# powerswitch.net
KiCad netlist of a schematic drawn in Altium Designer
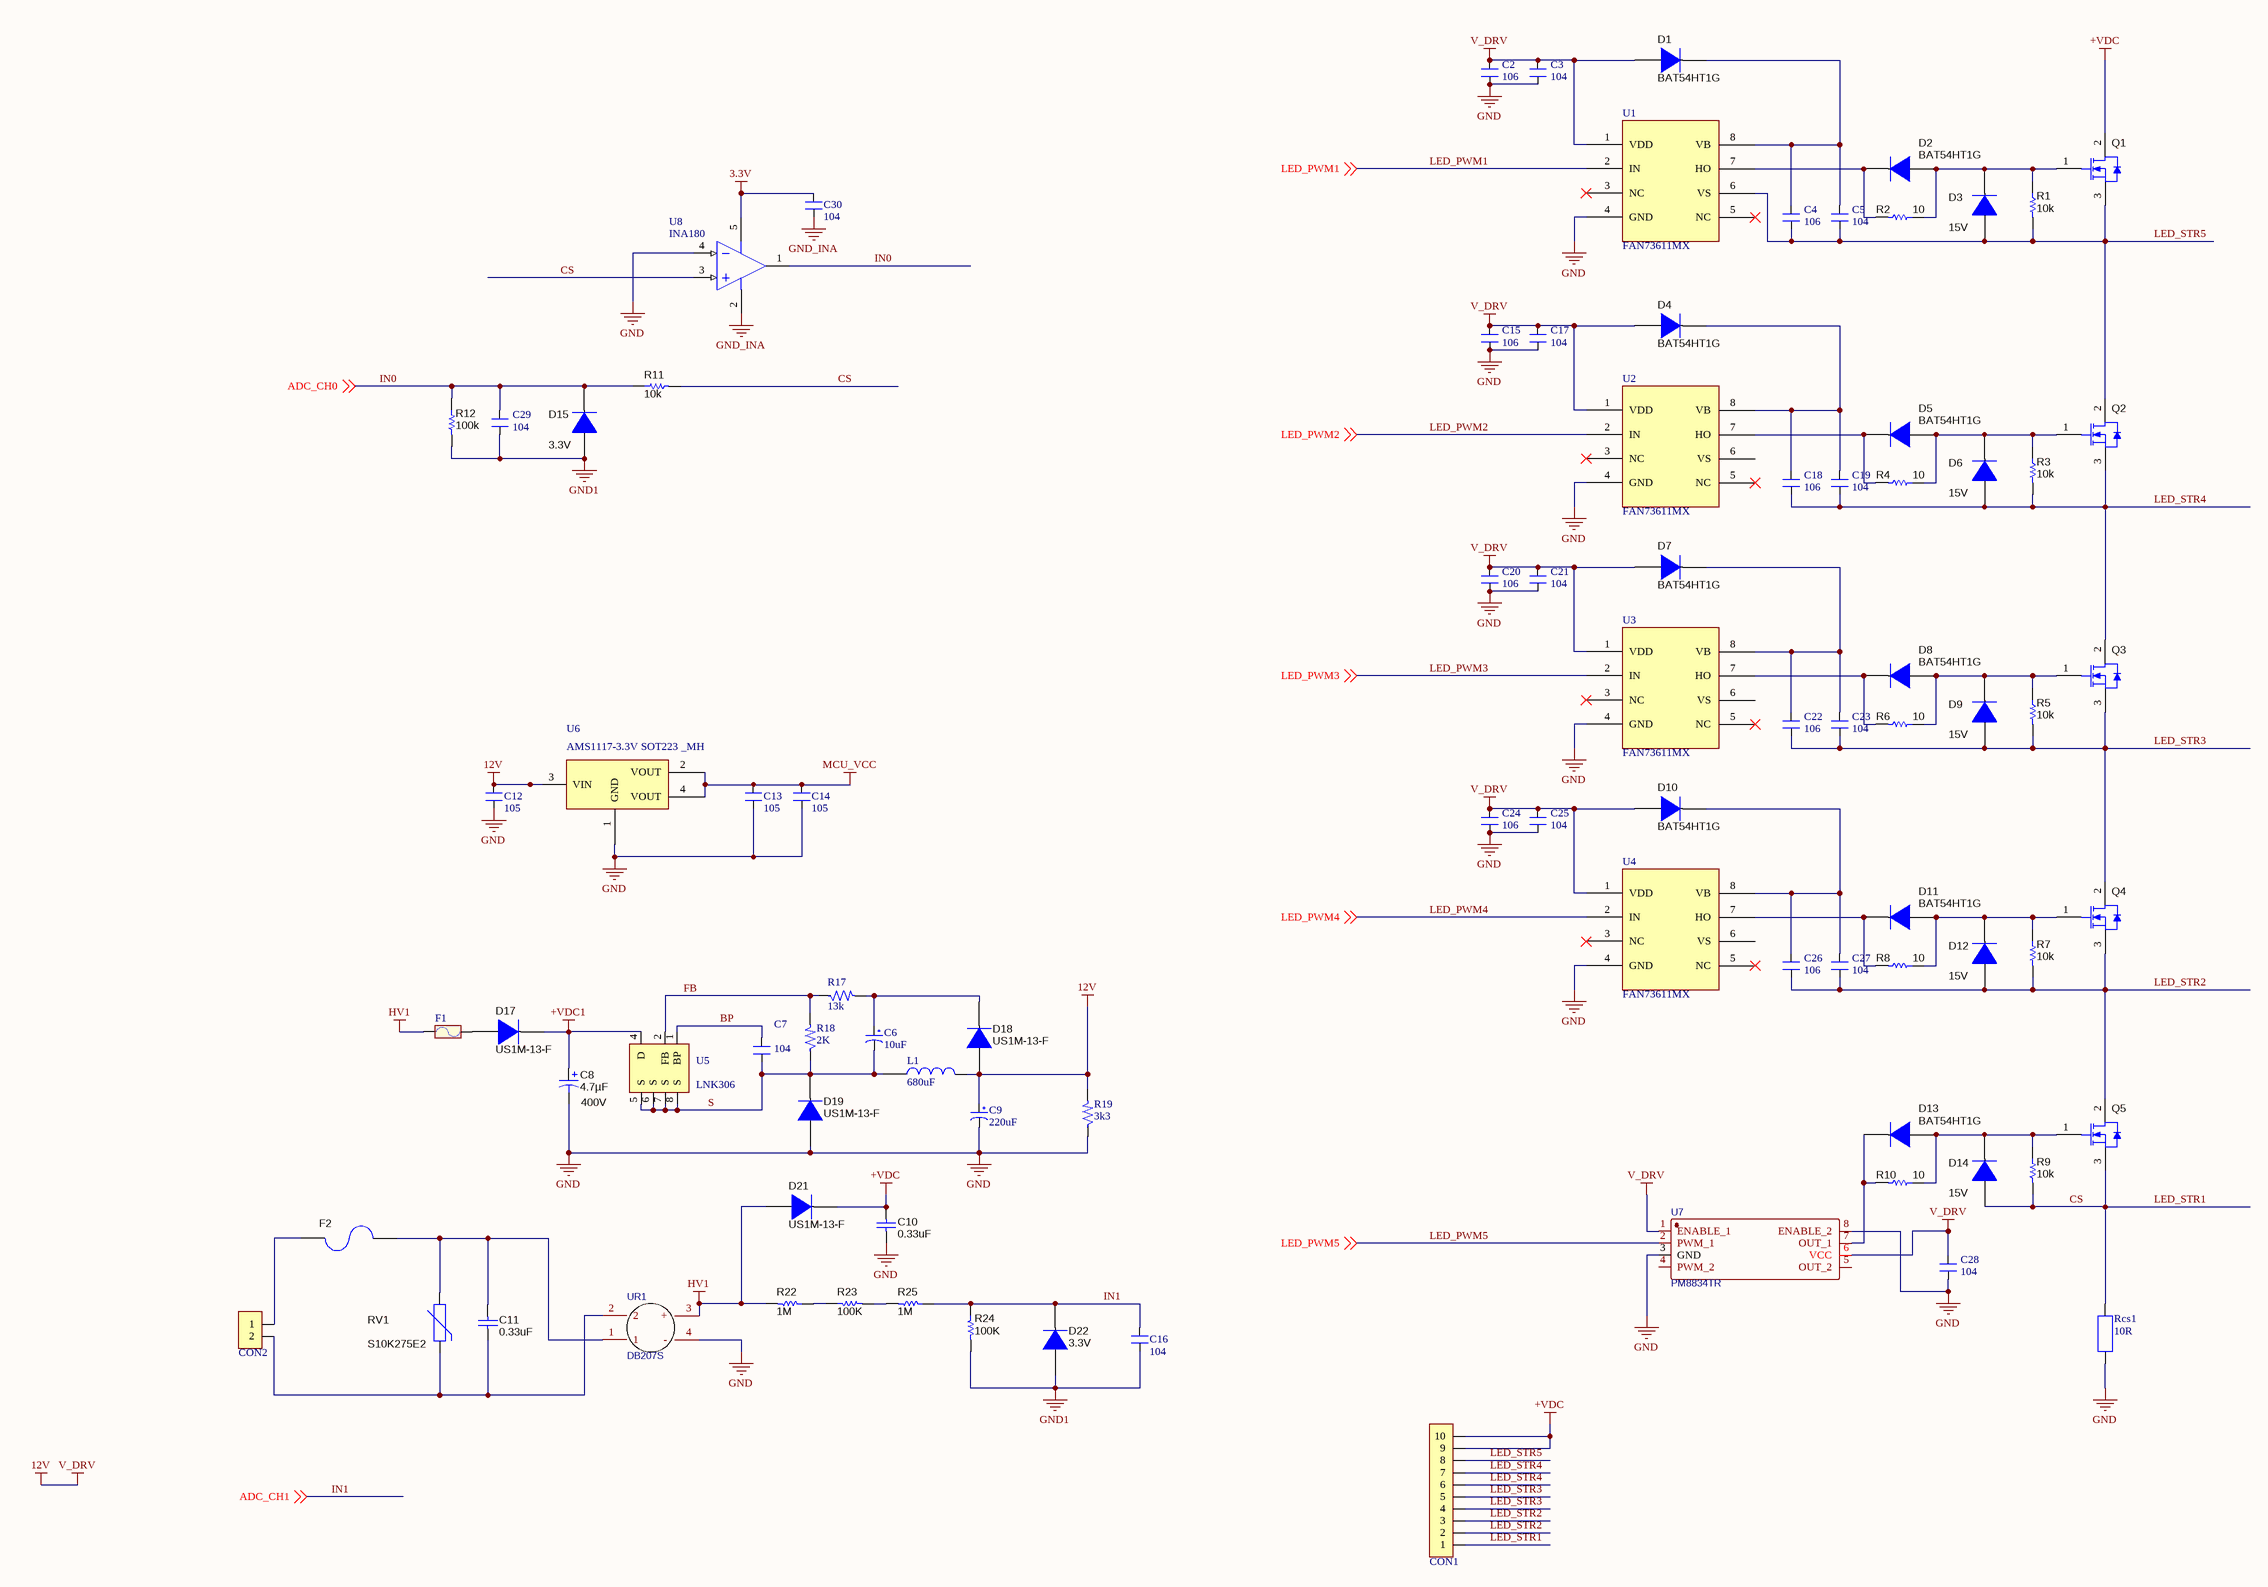
[diagram p0: powerswitch.SchDoc]

(export (version "E")
  (design (tool "Eeschema 10.0.6"))
  (components
    (comp (ref "C2")
      (value "106")
      (footprint "0805_HV")
      (description "Cap SMD")
      (libsource (lib "hatcatbietbay") (part "CM"))
    )
    (comp (ref "C3")
      (value "104")
      (footprint "0805_HV")
      (description "Cap SMD")
      (libsource (lib "hatcatbietbay") (part "CM"))
    )
    (comp (ref "C4")
      (value "106")
      (footprint "0805_HV")
      (description "Cap SMD")
      (libsource (lib "hatcatbietbay") (part "CM"))
    )
    (comp (ref "C5")
      (value "104")
      (footprint "0805_HV")
      (description "Cap SMD")
      (libsource (lib "hatcatbietbay") (part "CM"))
    )
    (comp (ref "C6")
      (value "10uF")
      (footprint "TU_NHOM_10uF_MH")
      (description "TU_NHOM_10uF_25V_MH")
      (libsource (lib "MH_DA_THU_VIEN_16122016") (part "TU_NHOM_10uF_25V_MH"))
    )
    (comp (ref "C7")
      (value "104")
      (footprint "0805_HV")
      (description "Cap SMD")
      (libsource (lib "hatcatbietbay") (part "CM"))
    )
    (comp (ref "C8")
      (value "400AX6R8M8x11")
      (footprint "CAP-PANACAP-G-GENERIC")
      (description "CAP, AL, 6.8uF, 400V, +/-20%, TH")
      (fields
        (field (name "VALUEDISPLAYED") "4.7µF")
        (field (name "MANUFACTURER") "Rubycon")
        (field (name "VALUE2") "400V")
        (field (name "PUBLISHER") "Texas Instruments")
      )
      (libsource (lib "Capacitor_Aluminum") (part "400AX6R8M8x11"))
    )
    (comp (ref "C9")
      (value "220uF")
      (footprint "TU_NHOM_2.5_MH")
      (description "TU_NHOM_220uF_25V_MH")
      (libsource (lib "MH_DA_THU_VIEN_16122016") (part "TU_NHOM_220uF_25V_MH"))
    )
    (comp (ref "C10")
      (value "0.33uF")
      (footprint "B32922_12mm")
      (description "CAP FILM 0.33UF 630VDC RADIAL")
      (fields
        (field (name "PARTNUMBER") "B32922C3334M189")
        (field (name "MANUFACTURER") "EPCOS(TDK)")
        (field (name "SYMBOLCREATOR") "x0199378")
      )
      (libsource (lib "All-Final Symbols") (part "BFC233620154"))
    )
    (comp (ref "C11")
      (value "0.33uF")
      (footprint "B32922_12mm")
      (description "CAP FILM 0.33UF 630VDC RADIAL")
      (fields
        (field (name "PARTNUMBER") "B32922C3334M189")
        (field (name "MANUFACTURER") "EPCOS(TDK)")
        (field (name "SYMBOLCREATOR") "x0199378")
      )
      (libsource (lib "All-Final Symbols") (part "BFC233620154"))
    )
    (comp (ref "C12")
      (value "105")
      (footprint "0805_HV")
      (description "Cap SMD")
      (libsource (lib "hatcatbietbay") (part "CM"))
    )
    (comp (ref "C13")
      (value "105")
      (footprint "0805_HV")
      (description "Cap SMD")
      (libsource (lib "hatcatbietbay") (part "CM"))
    )
    (comp (ref "C14")
      (value "105")
      (footprint "0805_HV")
      (description "Cap SMD")
      (libsource (lib "hatcatbietbay") (part "CM"))
    )
    (comp (ref "C15")
      (value "106")
      (footprint "0805_HV")
      (description "Cap SMD")
      (libsource (lib "hatcatbietbay") (part "CM"))
    )
    (comp (ref "C16")
      (value "104")
      (footprint "0805_HV")
      (description "Cap SMD")
      (libsource (lib "hatcatbietbay") (part "CM"))
    )
    (comp (ref "C17")
      (value "104")
      (footprint "0805_HV")
      (description "Cap SMD")
      (libsource (lib "hatcatbietbay") (part "CM"))
    )
    (comp (ref "C18")
      (value "106")
      (footprint "0805_HV")
      (description "Cap SMD")
      (libsource (lib "hatcatbietbay") (part "CM"))
    )
    (comp (ref "C19")
      (value "104")
      (footprint "0805_HV")
      (description "Cap SMD")
      (libsource (lib "hatcatbietbay") (part "CM"))
    )
    (comp (ref "C20")
      (value "106")
      (footprint "0805_HV")
      (description "Cap SMD")
      (libsource (lib "hatcatbietbay") (part "CM"))
    )
    (comp (ref "C21")
      (value "104")
      (footprint "0805_HV")
      (description "Cap SMD")
      (libsource (lib "hatcatbietbay") (part "CM"))
    )
    (comp (ref "C22")
      (value "106")
      (footprint "0805_HV")
      (description "Cap SMD")
      (libsource (lib "hatcatbietbay") (part "CM"))
    )
    (comp (ref "C23")
      (value "104")
      (footprint "0805_HV")
      (description "Cap SMD")
      (libsource (lib "hatcatbietbay") (part "CM"))
    )
    (comp (ref "C24")
      (value "106")
      (footprint "0805_HV")
      (description "Cap SMD")
      (libsource (lib "hatcatbietbay") (part "CM"))
    )
    (comp (ref "C25")
      (value "104")
      (footprint "0805_HV")
      (description "Cap SMD")
      (libsource (lib "hatcatbietbay") (part "CM"))
    )
    (comp (ref "C26")
      (value "106")
      (footprint "0805_HV")
      (description "Cap SMD")
      (libsource (lib "hatcatbietbay") (part "CM"))
    )
    (comp (ref "C27")
      (value "104")
      (footprint "0805_HV")
      (description "Cap SMD")
      (libsource (lib "hatcatbietbay") (part "CM"))
    )
    (comp (ref "C28")
      (value "104")
      (footprint "0805_HV")
      (description "Cap SMD")
      (libsource (lib "hatcatbietbay") (part "CM"))
    )
    (comp (ref "C29")
      (value "104")
      (footprint "0805_HV")
      (description "Cap SMD")
      (libsource (lib "hatcatbietbay") (part "CM"))
    )
    (comp (ref "C30")
      (value "104")
      (footprint "0805_HV")
      (description "Cap SMD")
      (libsource (lib "hatcatbietbay") (part "CM"))
    )
    (comp (ref "CON1")
      (value "CON 10 EDG 5.08_MH")
      (footprint "Con 10 EDG 5.08")
      (description "CON 10 EDG 5.08 (xanh cong)")
      (libsource (lib "MH_DA_THU_VIEN_16122016") (part "CON 10 EDG 5.08_MH"))
    )
    (comp (ref "CON2")
      (value "CON 2 EDG 5.08_MH")
      (footprint "CON 2 EDG 5.08")
      (description "CON 2 EDG 5.08 (xanh cong)")
      (libsource (lib "mySch") (part "CON 2 EDG 5.08_MH"))
    )
    (comp (ref "D1")
      (value "BAT54HT1G")
      (footprint "SOD-323")
      (description "Diode, Switching, 100 V, 0.2 A, SOD-323")
      (fields
        (field (name "MANUFACTURER") "Micro Commercial Components")
        (field (name "PUBLISHER") "Texas Instruments")
      )
      (libsource (lib "Diode") (part "MMDL914-TP"))
    )
    (comp (ref "D2")
      (value "BAT54HT1G")
      (footprint "SOD-323")
      (description "Diode, Switching, 100 V, 0.2 A, SOD-323")
      (fields
        (field (name "MANUFACTURER") "Micro Commercial Components")
        (field (name "PUBLISHER") "Texas Instruments")
      )
      (libsource (lib "Diode") (part "MMDL914-TP"))
    )
    (comp (ref "D3")
      (value "15V")
      (footprint "SOD-323")
      (description "Diode, Switching, 100 V, 0.2 A, SOD-323")
      (fields
        (field (name "PARTNUMBER") "BAV21W-7-F")
        (field (name "MANUFACTURER") "Micro Commercial Components")
        (field (name "PUBLISHER") "Texas Instruments")
      )
      (libsource (lib "Diode") (part "MMDL914-TP"))
    )
    (comp (ref "D4")
      (value "BAT54HT1G")
      (footprint "SOD-323")
      (description "Diode, Switching, 100 V, 0.2 A, SOD-323")
      (fields
        (field (name "MANUFACTURER") "Micro Commercial Components")
        (field (name "PUBLISHER") "Texas Instruments")
      )
      (libsource (lib "Diode") (part "MMDL914-TP"))
    )
    (comp (ref "D5")
      (value "BAT54HT1G")
      (footprint "SOD-323")
      (description "Diode, Switching, 100 V, 0.2 A, SOD-323")
      (fields
        (field (name "MANUFACTURER") "Micro Commercial Components")
        (field (name "PUBLISHER") "Texas Instruments")
      )
      (libsource (lib "Diode") (part "MMDL914-TP"))
    )
    (comp (ref "D6")
      (value "15V")
      (footprint "SOD-323")
      (description "Diode, Switching, 100 V, 0.2 A, SOD-323")
      (fields
        (field (name "PARTNUMBER") "BAV21W-7-F")
        (field (name "MANUFACTURER") "Micro Commercial Components")
        (field (name "PUBLISHER") "Texas Instruments")
      )
      (libsource (lib "Diode") (part "MMDL914-TP"))
    )
    (comp (ref "D7")
      (value "BAT54HT1G")
      (footprint "SOD-323")
      (description "Diode, Switching, 100 V, 0.2 A, SOD-323")
      (fields
        (field (name "MANUFACTURER") "Micro Commercial Components")
        (field (name "PUBLISHER") "Texas Instruments")
      )
      (libsource (lib "Diode") (part "MMDL914-TP"))
    )
    (comp (ref "D8")
      (value "BAT54HT1G")
      (footprint "SOD-323")
      (description "Diode, Switching, 100 V, 0.2 A, SOD-323")
      (fields
        (field (name "MANUFACTURER") "Micro Commercial Components")
        (field (name "PUBLISHER") "Texas Instruments")
      )
      (libsource (lib "Diode") (part "MMDL914-TP"))
    )
    (comp (ref "D9")
      (value "15V")
      (footprint "SOD-323")
      (description "Diode, Switching, 100 V, 0.2 A, SOD-323")
      (fields
        (field (name "PARTNUMBER") "BAV21W-7-F")
        (field (name "MANUFACTURER") "Micro Commercial Components")
        (field (name "PUBLISHER") "Texas Instruments")
      )
      (libsource (lib "Diode") (part "MMDL914-TP"))
    )
    (comp (ref "D10")
      (value "BAT54HT1G")
      (footprint "SOD-323")
      (description "Diode, Switching, 100 V, 0.2 A, SOD-323")
      (fields
        (field (name "MANUFACTURER") "Micro Commercial Components")
        (field (name "PUBLISHER") "Texas Instruments")
      )
      (libsource (lib "Diode") (part "MMDL914-TP"))
    )
    (comp (ref "D11")
      (value "BAT54HT1G")
      (footprint "SOD-323")
      (description "Diode, Switching, 100 V, 0.2 A, SOD-323")
      (fields
        (field (name "MANUFACTURER") "Micro Commercial Components")
        (field (name "PUBLISHER") "Texas Instruments")
      )
      (libsource (lib "Diode") (part "MMDL914-TP"))
    )
    (comp (ref "D12")
      (value "15V")
      (footprint "SOD-323")
      (description "Diode, Switching, 100 V, 0.2 A, SOD-323")
      (fields
        (field (name "PARTNUMBER") "BAV21W-7-F")
        (field (name "MANUFACTURER") "Micro Commercial Components")
        (field (name "PUBLISHER") "Texas Instruments")
      )
      (libsource (lib "Diode") (part "MMDL914-TP"))
    )
    (comp (ref "D13")
      (value "BAT54HT1G")
      (footprint "SOD-323")
      (description "Diode, Switching, 100 V, 0.2 A, SOD-323")
      (fields
        (field (name "MANUFACTURER") "Micro Commercial Components")
        (field (name "PUBLISHER") "Texas Instruments")
      )
      (libsource (lib "Diode") (part "MMDL914-TP"))
    )
    (comp (ref "D14")
      (value "15V")
      (footprint "SOD-323")
      (description "Diode, Switching, 100 V, 0.2 A, SOD-323")
      (fields
        (field (name "PARTNUMBER") "BAV21W-7-F")
        (field (name "MANUFACTURER") "Micro Commercial Components")
        (field (name "PUBLISHER") "Texas Instruments")
      )
      (libsource (lib "Diode") (part "MMDL914-TP"))
    )
    (comp (ref "D15")
      (value "3.3V")
      (footprint "SOD-323")
      (description "Diode, Switching, 100 V, 0.2 A, SOD-323")
      (fields
        (field (name "PARTNUMBER") "BAV21W-7-F")
        (field (name "MANUFACTURER") "Micro Commercial Components")
        (field (name "PUBLISHER") "Texas Instruments")
      )
      (libsource (lib "Diode") (part "MMDL914-TP"))
    )
    (comp (ref "D17")
      (value "US1M-13-F")
      (footprint "SMB")
      (description "Diode, Ultrafast, 600V, 1A, SMB")
      (fields
        (field (name "PARTNUMBER") "US1M-13-F")
        (field (name "MANUFACTURER") "Diodes Inc.")
        (field (name "PUBLISHER") "Texas Instruments")
      )
      (libsource (lib "Diode") (part "MURS160-13-F"))
    )
    (comp (ref "D18")
      (value "US1M-13-F")
      (footprint "SMB")
      (description "Diode, Ultrafast, 600V, 1A, SMB")
      (fields
        (field (name "PARTNUMBER") "US1M-13-F")
        (field (name "MANUFACTURER") "Diodes Inc.")
        (field (name "PUBLISHER") "Texas Instruments")
      )
      (libsource (lib "Diode") (part "MURS160-13-F"))
    )
    (comp (ref "D19")
      (value "US1M-13-F")
      (footprint "SMB")
      (description "Diode, Ultrafast, 600V, 1A, SMB")
      (fields
        (field (name "PARTNUMBER") "US1M-13-F")
        (field (name "MANUFACTURER") "Diodes Inc.")
        (field (name "PUBLISHER") "Texas Instruments")
      )
      (libsource (lib "Diode") (part "MURS160-13-F"))
    )
    (comp (ref "D21")
      (value "US1M-13-F")
      (footprint "SMB")
      (description "Diode, Ultrafast, 600V, 1A, SMB")
      (fields
        (field (name "PARTNUMBER") "US1M-13-F")
        (field (name "MANUFACTURER") "Diodes Inc.")
        (field (name "PUBLISHER") "Texas Instruments")
      )
      (libsource (lib "Diode") (part "MURS160-13-F"))
    )
    (comp (ref "D22")
      (value "3.3V")
      (footprint "SOD-323")
      (description "Diode, Switching, 100 V, 0.2 A, SOD-323")
      (fields
        (field (name "PARTNUMBER") "BAV21W-7-F")
        (field (name "MANUFACTURER") "Micro Commercial Components")
        (field (name "PUBLISHER") "Texas Instruments")
      )
      (libsource (lib "Diode") (part "MMDL914-TP"))
    )
    (comp (ref "F1")
      (value "FUSE_AUTO_0.5A 8V 1206_MH")
      (footprint "FUSE 1206")
      (description "Fuse")
      (libsource (lib "MH_DA_THU_VIEN_16122016") (part "FUSE_AUTO_0.5A 8V 1206_MH"))
    )
    (comp (ref "F2")
      (value "37015000430")
      (footprint "Fuse 5x20")
      (description "FUSE BOARD MOUNT 5A 250VAC RAD")
      (fields (field (name "MANUFACTURER") "Littelfuse Inc") (field (name "PUBLISHER") "Texas Instruments"))
      (libsource (lib "Fuse") (part "0216008.MXESPP"))
    )
    (comp (ref "L1")
      (value "680uF")
      (footprint "Inductor 4.5x5")
      (libsource (lib "MH_DA_THU_VIEN_16122016") (part "Inductor 4.5x5_MH"))
    )
    (comp (ref "Q1")
      (value "IPA60R330P")
      (footprint "TO-220AB_NH")
      (description "MOSFET N-CH 600V 10.6A TO220")
      (fields
        (field (name "PARTNUMBER") "IPA60R330P6XKSA1")
        (field (name "MANUFACTURER") "Infineon Technologies")
        (field (name "SYMBOLCREATOR") "x0199378")
      )
      (libsource (lib "Final symbols") (part "IPP60R190P6"))
    )
    (comp (ref "Q2")
      (value "IPA60R330P")
      (footprint "TO-220AB_NH")
      (description "MOSFET N-CH 600V 10.6A TO220")
      (fields
        (field (name "PARTNUMBER") "IPA60R330P6XKSA1")
        (field (name "MANUFACTURER") "Infineon Technologies")
        (field (name "SYMBOLCREATOR") "x0199378")
      )
      (libsource (lib "Final symbols") (part "IPP60R190P6"))
    )
    (comp (ref "Q3")
      (value "IPA60R330P")
      (footprint "TO-220AB_NH")
      (description "MOSFET N-CH 600V 10.6A TO220")
      (fields
        (field (name "PARTNUMBER") "IPA60R330P6XKSA1")
        (field (name "MANUFACTURER") "Infineon Technologies")
        (field (name "SYMBOLCREATOR") "x0199378")
      )
      (libsource (lib "Final symbols") (part "IPP60R190P6"))
    )
    (comp (ref "Q4")
      (value "IPA60R330P")
      (footprint "TO-220AB_NH")
      (description "MOSFET N-CH 600V 10.6A TO220")
      (fields
        (field (name "PARTNUMBER") "IPA60R330P6XKSA1")
        (field (name "MANUFACTURER") "Infineon Technologies")
        (field (name "SYMBOLCREATOR") "x0199378")
      )
      (libsource (lib "Final symbols") (part "IPP60R190P6"))
    )
    (comp (ref "Q5")
      (value "IPA60R330P")
      (footprint "TO-220AB_NH")
      (description "MOSFET N-CH 600V 10.6A TO220")
      (fields
        (field (name "PARTNUMBER") "IPA60R330P6XKSA1")
        (field (name "MANUFACTURER") "Infineon Technologies")
        (field (name "SYMBOLCREATOR") "x0199378")
      )
      (libsource (lib "Final symbols") (part "IPP60R190P6"))
    )
    (comp (ref "R1")
      (value "10k")
      (footprint "Tro SMD 0805")
      (description "RES, 100, 1%, 0.1 W, 0402")
      (fields
        (field (name "PARTNUMBER") "ERJ-2RKF1000X")
        (field (name "MANUFACTURER") "Panasonic")
        (field (name "PUBLISHER") "Texas Instruments")
      )
      (libsource (lib "mySch") (part "R nho"))
    )
    (comp (ref "R2")
      (value "10")
      (footprint "Tro SMD 0805")
      (description "RES, 100, 1%, 0.1 W, 0402")
      (fields
        (field (name "PARTNUMBER") "ERJ-2RKF1000X")
        (field (name "MANUFACTURER") "Panasonic")
        (field (name "PUBLISHER") "Texas Instruments")
      )
      (libsource (lib "mySch") (part "R nho"))
    )
    (comp (ref "R3")
      (value "10k")
      (footprint "Tro SMD 0805")
      (description "RES, 100, 1%, 0.1 W, 0402")
      (fields
        (field (name "PARTNUMBER") "ERJ-2RKF1000X")
        (field (name "MANUFACTURER") "Panasonic")
        (field (name "PUBLISHER") "Texas Instruments")
      )
      (libsource (lib "mySch") (part "R nho"))
    )
    (comp (ref "R4")
      (value "10")
      (footprint "Tro SMD 0805")
      (description "RES, 100, 1%, 0.1 W, 0402")
      (fields
        (field (name "PARTNUMBER") "ERJ-2RKF1000X")
        (field (name "MANUFACTURER") "Panasonic")
        (field (name "PUBLISHER") "Texas Instruments")
      )
      (libsource (lib "mySch") (part "R nho"))
    )
    (comp (ref "R5")
      (value "10k")
      (footprint "Tro SMD 0805")
      (description "RES, 100, 1%, 0.1 W, 0402")
      (fields
        (field (name "PARTNUMBER") "ERJ-2RKF1000X")
        (field (name "MANUFACTURER") "Panasonic")
        (field (name "PUBLISHER") "Texas Instruments")
      )
      (libsource (lib "mySch") (part "R nho"))
    )
    (comp (ref "R6")
      (value "10")
      (footprint "Tro SMD 0805")
      (description "RES, 100, 1%, 0.1 W, 0402")
      (fields
        (field (name "PARTNUMBER") "ERJ-2RKF1000X")
        (field (name "MANUFACTURER") "Panasonic")
        (field (name "PUBLISHER") "Texas Instruments")
      )
      (libsource (lib "mySch") (part "R nho"))
    )
    (comp (ref "R7")
      (value "10k")
      (footprint "Tro SMD 0805")
      (description "RES, 100, 1%, 0.1 W, 0402")
      (fields
        (field (name "PARTNUMBER") "ERJ-2RKF1000X")
        (field (name "MANUFACTURER") "Panasonic")
        (field (name "PUBLISHER") "Texas Instruments")
      )
      (libsource (lib "mySch") (part "R nho"))
    )
    (comp (ref "R8")
      (value "10")
      (footprint "Tro SMD 0805")
      (description "RES, 100, 1%, 0.1 W, 0402")
      (fields
        (field (name "PARTNUMBER") "ERJ-2RKF1000X")
        (field (name "MANUFACTURER") "Panasonic")
        (field (name "PUBLISHER") "Texas Instruments")
      )
      (libsource (lib "mySch") (part "R nho"))
    )
    (comp (ref "R9")
      (value "10k")
      (footprint "Tro SMD 0805")
      (description "RES, 100, 1%, 0.1 W, 0402")
      (fields
        (field (name "PARTNUMBER") "ERJ-2RKF1000X")
        (field (name "MANUFACTURER") "Panasonic")
        (field (name "PUBLISHER") "Texas Instruments")
      )
      (libsource (lib "mySch") (part "R nho"))
    )
    (comp (ref "R10")
      (value "10")
      (footprint "Tro SMD 0805")
      (description "RES, 100, 1%, 0.1 W, 0402")
      (fields
        (field (name "PARTNUMBER") "ERJ-2RKF1000X")
        (field (name "MANUFACTURER") "Panasonic")
        (field (name "PUBLISHER") "Texas Instruments")
      )
      (libsource (lib "mySch") (part "R nho"))
    )
    (comp (ref "R11")
      (value "10k")
      (footprint "Tro SMD 0805")
      (description "RES, 100, 1%, 0.1 W, 0402")
      (fields
        (field (name "PARTNUMBER") "ERJ-2RKF1000X")
        (field (name "MANUFACTURER") "Panasonic")
        (field (name "PUBLISHER") "Texas Instruments")
      )
      (libsource (lib "mySch") (part "R nho"))
    )
    (comp (ref "R12")
      (value "100k")
      (footprint "Tro SMD 0805")
      (description "RES, 100, 1%, 0.1 W, 0402")
      (fields
        (field (name "PARTNUMBER") "ERJ-2RKF1000X")
        (field (name "MANUFACTURER") "Panasonic")
        (field (name "PUBLISHER") "Texas Instruments")
      )
      (libsource (lib "mySch") (part "R nho"))
    )
    (comp (ref "R17")
      (value "13k")
      (footprint "0805_HV")
      (description "Resistor 1/4W")
      (libsource (lib "hatcatbietbay") (part "R"))
    )
    (comp (ref "R18")
      (value "2K")
      (footprint "0805_HV")
      (description "Resistor 1/4W")
      (libsource (lib "hatcatbietbay") (part "R"))
    )
    (comp (ref "R19")
      (value "3k3")
      (footprint "0805_HV")
      (description "Resistor 1/4W")
      (libsource (lib "hatcatbietbay") (part "R"))
    )
    (comp (ref "R22")
      (value "1M")
      (footprint "1206")
      (description "RES, 100, 1%, 0.1 W, 0402")
      (fields
        (field (name "PARTNUMBER") "ERJ-2RKF1000X")
        (field (name "MANUFACTURER") "Panasonic")
        (field (name "PUBLISHER") "Texas Instruments")
      )
      (libsource (lib "mySch") (part "R nho"))
    )
    (comp (ref "R23")
      (value "100K")
      (footprint "1206")
      (description "RES, 100, 1%, 0.1 W, 0402")
      (fields
        (field (name "PARTNUMBER") "ERJ-2RKF1000X")
        (field (name "MANUFACTURER") "Panasonic")
        (field (name "PUBLISHER") "Texas Instruments")
      )
      (libsource (lib "mySch") (part "R nho"))
    )
    (comp (ref "R24")
      (value "100K")
      (footprint "1206")
      (description "RES, 100, 1%, 0.1 W, 0402")
      (fields
        (field (name "PARTNUMBER") "ERJ-2RKF1000X")
        (field (name "MANUFACTURER") "Panasonic")
        (field (name "PUBLISHER") "Texas Instruments")
      )
      (libsource (lib "mySch") (part "R nho"))
    )
    (comp (ref "R25")
      (value "1M")
      (footprint "1206")
      (description "RES, 100, 1%, 0.1 W, 0402")
      (fields
        (field (name "PARTNUMBER") "ERJ-2RKF1000X")
        (field (name "MANUFACTURER") "Panasonic")
        (field (name "PUBLISHER") "Texas Instruments")
      )
      (libsource (lib "mySch") (part "R nho"))
    )
    (comp (ref "Rcs1")
      (value "10R")
      (footprint "TRO_VACH_2W")
      (libsource (lib "MH_DA_THU_VIEN_16122016") (part "TRO_CS_2W_MH"))
    )
    (comp (ref "RV1")
      (value "S10K275E2")
      (footprint "VAR_S10K275E2")
      (description "Varistor 275V RMS 10MM Radial, TH")
      (fields
        (field (name "MANUFACTURER") "EPCOS Inc")
        (field (name "SYMBOLCREATOR") "a0412235")
        (field (name "PUBLISHER") "Texas Instruments")
      )
      (libsource (lib "Other_Passive") (part "S10K275E2"))
    )
    (comp (ref "U1") (value "FAN73611MX") (footprint "SOP 8") (libsource (lib "Schlib1") (part "FAN73611MX")))
    (comp (ref "U2") (value "FAN73611MX") (footprint "SOP 8") (libsource (lib "Schlib1") (part "FAN73611MX")))
    (comp (ref "U3") (value "FAN73611MX") (footprint "SOP 8") (libsource (lib "Schlib1") (part "FAN73611MX")))
    (comp (ref "U4") (value "FAN73611MX") (footprint "SOP 8") (libsource (lib "Schlib1") (part "FAN73611MX")))
    (comp (ref "U5") (value "LNK306") (footprint "SOP 7") (libsource (lib "LNK304") (part "Component_1")))
    (comp (ref "U6")
      (value "AMS1117-3.3V SOT223 _MH")
      (footprint "SOT223")
      (libsource (lib "MH_DA_THU_VIEN_16122016") (part "AMS1117-3.3V SOT223 _MH"))
    )
    (comp (ref "U7")
      (value "PM8834TR")
      (footprint "SOP 8")
      (fields (field (name "BOM_SUPPLIER PART") "C221495") (field (name "CONTRIBUTOR") "LCSC"))
      (libsource (lib "Schlib1") (part "PM8834TR"))
    )
    (comp (ref "U8")
      (value "INA180")
      (footprint "SOT23-5AL")
      (description "Micropower Quad CMOS Voltage Comparator")
      (libsource (lib "Schlib1") (part "INA180"))
    )
    (comp (ref "UR1")
      (value "DB207S")
      (footprint "DB207S")
      (fields (field (name "BOM_SUPPLIER PART") "C84160"))
      (libsource (lib "mySch") (part "DB207S"))
    )
  )
  (nets
    (net (code "1") (name "+VDC") (class "Default")
      (node (ref "C10") (pin "2") (pinfunction "2_2") (pintype "passive"))
      (node (ref "CON1") (pin "10") (pinfunction "10_10") (pintype "passive"))
      (node (ref "CON1") (pin "9") (pinfunction "9_9") (pintype "passive"))
      (node (ref "D21") (pin "1") (pinfunction "K_1") (pintype "passive"))
      (node (ref "Q1") (pin "2") (pinfunction "D_2") (pintype "passive"))
    )
    (net (code "2") (name "+VDC1") (class "Default")
      (node (ref "C8") (pin "1") (pinfunction "+_1") (pintype "passive"))
      (node (ref "D17") (pin "1") (pinfunction "K_1") (pintype "passive"))
      (node (ref "U5") (pin "4") (pinfunction "D_4") (pintype "passive"))
    )
    (net (code "3") (name "/BP") (class "Default")
      (node (ref "C7") (pin "2") (pinfunction "2_2") (pintype "passive"))
      (node (ref "U5") (pin "1") (pinfunction "BP_1") (pintype "passive"))
    )
    (net (code "4") (name "/CS") (class "Default")
      (node (ref "CON1") (pin "1") (pinfunction "1_1") (pintype "passive"))
      (node (ref "D14") (pin "2") (pinfunction "A_2") (pintype "passive"))
      (node (ref "Q5") (pin "3") (pinfunction "S_3") (pintype "passive"))
      (node (ref "R11") (pin "2") (pinfunction "2_2") (pintype "passive"))
      (node (ref "R9") (pin "2") (pinfunction "2_2") (pintype "passive"))
      (node (ref "Rcs1") (pin "2") (pinfunction "2_2") (pintype "passive"))
      (node (ref "U8") (pin "3") (pinfunction "IN+_3") (pintype "input"))
    )
    (net (code "5") (name "/FB") (class "Default")
      (node (ref "R17") (pin "1") (pinfunction "1_1") (pintype "passive"))
      (node (ref "R18") (pin "2") (pinfunction "2_2") (pintype "passive"))
      (node (ref "U5") (pin "2") (pinfunction "FB_2") (pintype "passive"))
    )
    (net (code "6") (name "/LED_STR2") (class "Default")
      (node (ref "C26") (pin "1") (pinfunction "1_1") (pintype "passive"))
      (node (ref "C27") (pin "1") (pinfunction "1_1") (pintype "passive"))
      (node (ref "CON1") (pin "2") (pinfunction "2_2") (pintype "passive"))
      (node (ref "CON1") (pin "3") (pinfunction "3_3") (pintype "passive"))
      (node (ref "D12") (pin "2") (pinfunction "A_2") (pintype "passive"))
      (node (ref "Q4") (pin "3") (pinfunction "S_3") (pintype "passive"))
      (node (ref "Q5") (pin "2") (pinfunction "D_2") (pintype "passive"))
      (node (ref "R7") (pin "2") (pinfunction "2_2") (pintype "passive"))
    )
    (net (code "7") (name "/LED_STR3") (class "Default")
      (node (ref "C22") (pin "1") (pinfunction "1_1") (pintype "passive"))
      (node (ref "C23") (pin "1") (pinfunction "1_1") (pintype "passive"))
      (node (ref "CON1") (pin "4") (pinfunction "4_4") (pintype "passive"))
      (node (ref "CON1") (pin "5") (pinfunction "5_5") (pintype "passive"))
      (node (ref "D9") (pin "2") (pinfunction "A_2") (pintype "passive"))
      (node (ref "Q3") (pin "3") (pinfunction "S_3") (pintype "passive"))
      (node (ref "Q4") (pin "2") (pinfunction "D_2") (pintype "passive"))
      (node (ref "R5") (pin "2") (pinfunction "2_2") (pintype "passive"))
    )
    (net (code "8") (name "/LED_STR4") (class "Default")
      (node (ref "C18") (pin "1") (pinfunction "1_1") (pintype "passive"))
      (node (ref "C19") (pin "1") (pinfunction "1_1") (pintype "passive"))
      (node (ref "CON1") (pin "6") (pinfunction "6_6") (pintype "passive"))
      (node (ref "CON1") (pin "7") (pinfunction "7_7") (pintype "passive"))
      (node (ref "D6") (pin "2") (pinfunction "A_2") (pintype "passive"))
      (node (ref "Q2") (pin "3") (pinfunction "S_3") (pintype "passive"))
      (node (ref "Q3") (pin "2") (pinfunction "D_2") (pintype "passive"))
      (node (ref "R3") (pin "2") (pinfunction "2_2") (pintype "passive"))
    )
    (net (code "9") (name "/LED_STR5") (class "Default")
      (node (ref "C4") (pin "1") (pinfunction "1_1") (pintype "passive"))
      (node (ref "C5") (pin "1") (pinfunction "1_1") (pintype "passive"))
      (node (ref "CON1") (pin "8") (pinfunction "8_8") (pintype "passive"))
      (node (ref "D3") (pin "2") (pinfunction "A_2") (pintype "passive"))
      (node (ref "Q1") (pin "3") (pinfunction "S_3") (pintype "passive"))
      (node (ref "Q2") (pin "2") (pinfunction "D_2") (pintype "passive"))
      (node (ref "R1") (pin "2") (pinfunction "2_2") (pintype "passive"))
      (node (ref "U1") (pin "6") (pinfunction "VS_6") (pintype "passive"))
    )
    (net (code "10") (name "/S") (class "Default")
      (node (ref "C6") (pin "2") (pinfunction "2_2") (pintype "passive"))
      (node (ref "C7") (pin "1") (pinfunction "1_1") (pintype "passive"))
      (node (ref "D19") (pin "1") (pinfunction "K_1") (pintype "passive"))
      (node (ref "L1") (pin "1") (pinfunction "1_1") (pintype "passive"))
      (node (ref "R18") (pin "1") (pinfunction "1_1") (pintype "passive"))
      (node (ref "U5") (pin "5") (pinfunction "S_5") (pintype "passive"))
      (node (ref "U5") (pin "6") (pinfunction "S_6") (pintype "passive"))
      (node (ref "U5") (pin "7") (pinfunction "S_7") (pintype "passive"))
      (node (ref "U5") (pin "8") (pinfunction "S_8") (pintype "passive"))
    )
    (net (code "11") (name "3.3V") (class "Default")
      (node (ref "C30") (pin "2") (pinfunction "2_2") (pintype "passive"))
      (node (ref "U8") (pin "5") (pinfunction "V+_5") (pintype "power_in"))
    )
    (net (code "12") (name "12V") (class "Default")
      (node (ref "C12") (pin "2") (pinfunction "2_2") (pintype "passive"))
      (node (ref "C15") (pin "2") (pinfunction "2_2") (pintype "passive"))
      (node (ref "C17") (pin "2") (pinfunction "2_2") (pintype "passive"))
      (node (ref "C2") (pin "2") (pinfunction "2_2") (pintype "passive"))
      (node (ref "C20") (pin "2") (pinfunction "2_2") (pintype "passive"))
      (node (ref "C21") (pin "2") (pinfunction "2_2") (pintype "passive"))
      (node (ref "C24") (pin "2") (pinfunction "2_2") (pintype "passive"))
      (node (ref "C25") (pin "2") (pinfunction "2_2") (pintype "passive"))
      (node (ref "C28") (pin "2") (pinfunction "2_2") (pintype "passive"))
      (node (ref "C3") (pin "2") (pinfunction "2_2") (pintype "passive"))
      (node (ref "C9") (pin "1") (pinfunction "1_1") (pintype "passive"))
      (node (ref "D1") (pin "2") (pinfunction "A_2") (pintype "passive"))
      (node (ref "D10") (pin "2") (pinfunction "A_2") (pintype "passive"))
      (node (ref "D18") (pin "2") (pinfunction "A_2") (pintype "passive"))
      (node (ref "D4") (pin "2") (pinfunction "A_2") (pintype "passive"))
      (node (ref "D7") (pin "2") (pinfunction "A_2") (pintype "passive"))
      (node (ref "L1") (pin "2") (pinfunction "2_2") (pintype "passive"))
      (node (ref "R19") (pin "2") (pinfunction "2_2") (pintype "passive"))
      (node (ref "U1") (pin "1") (pinfunction "VDD_1") (pintype "passive"))
      (node (ref "U2") (pin "1") (pinfunction "VDD_1") (pintype "passive"))
      (node (ref "U3") (pin "1") (pinfunction "VDD_1") (pintype "passive"))
      (node (ref "U4") (pin "1") (pinfunction "VDD_1") (pintype "passive"))
      (node (ref "U6") (pin "3") (pinfunction "VIN_3") (pintype "passive"))
      (node (ref "U7") (pin "1") (pinfunction "ENABLE_1_1") (pintype "passive"))
      (node (ref "U7") (pin "6") (pinfunction "VCC_6") (pintype "passive"))
    )
    (net (code "13") (name "ADC_CH0") (class "Default")
      (node (ref "C29") (pin "2") (pinfunction "2_2") (pintype "passive"))
      (node (ref "D15") (pin "1") (pinfunction "K_1") (pintype "passive"))
      (node (ref "R11") (pin "1") (pinfunction "1_1") (pintype "passive"))
      (node (ref "R12") (pin "1") (pinfunction "1_1") (pintype "passive"))
      (node (ref "U8") (pin "1") (pinfunction "OUT_1") (pintype "open_collector"))
    )
    (net (code "14") (name "ADC_CH1") (class "Default")
      (node (ref "C16") (pin "2") (pinfunction "2_2") (pintype "passive"))
      (node (ref "D22") (pin "1") (pinfunction "K_1") (pintype "passive"))
      (node (ref "R24") (pin "1") (pinfunction "1_1") (pintype "passive"))
      (node (ref "R25") (pin "1") (pinfunction "1_1") (pintype "passive"))
    )
    (net (code "15") (name "GND") (class "Default")
      (node (ref "C10") (pin "1") (pinfunction "1_1") (pintype "passive"))
      (node (ref "C12") (pin "1") (pinfunction "1_1") (pintype "passive"))
      (node (ref "C13") (pin "1") (pinfunction "1_1") (pintype "passive"))
      (node (ref "C14") (pin "1") (pinfunction "1_1") (pintype "passive"))
      (node (ref "C15") (pin "1") (pinfunction "1_1") (pintype "passive"))
      (node (ref "C17") (pin "1") (pinfunction "1_1") (pintype "passive"))
      (node (ref "C2") (pin "1") (pinfunction "1_1") (pintype "passive"))
      (node (ref "C20") (pin "1") (pinfunction "1_1") (pintype "passive"))
      (node (ref "C21") (pin "1") (pinfunction "1_1") (pintype "passive"))
      (node (ref "C24") (pin "1") (pinfunction "1_1") (pintype "passive"))
      (node (ref "C25") (pin "1") (pinfunction "1_1") (pintype "passive"))
      (node (ref "C28") (pin "1") (pinfunction "1_1") (pintype "passive"))
      (node (ref "C3") (pin "1") (pinfunction "1_1") (pintype "passive"))
      (node (ref "C8") (pin "2") (pinfunction "-_2") (pintype "passive"))
      (node (ref "C9") (pin "2") (pinfunction "2_2") (pintype "passive"))
      (node (ref "D19") (pin "2") (pinfunction "A_2") (pintype "passive"))
      (node (ref "R19") (pin "1") (pinfunction "1_1") (pintype "passive"))
      (node (ref "Rcs1") (pin "1") (pinfunction "1_1") (pintype "passive"))
      (node (ref "U1") (pin "4") (pinfunction "GND_4") (pintype "passive"))
      (node (ref "U2") (pin "4") (pinfunction "GND_4") (pintype "passive"))
      (node (ref "U3") (pin "4") (pinfunction "GND_4") (pintype "passive"))
      (node (ref "U4") (pin "4") (pinfunction "GND_4") (pintype "passive"))
      (node (ref "U6") (pin "1") (pinfunction "GND_1") (pintype "passive"))
      (node (ref "U7") (pin "3") (pinfunction "GND_3") (pintype "passive"))
      (node (ref "U7") (pin "8") (pinfunction "ENABLE_2_8") (pintype "passive"))
      (node (ref "U8") (pin "4") (pinfunction "IN-_4") (pintype "input"))
      (node (ref "UR1") (pin "4") (pinfunction "-_4") (pintype "passive"))
    )
    (net (code "16") (name "GND1") (class "Default")
      (node (ref "C16") (pin "1") (pinfunction "1_1") (pintype "passive"))
      (node (ref "C29") (pin "1") (pinfunction "1_1") (pintype "passive"))
      (node (ref "D15") (pin "2") (pinfunction "A_2") (pintype "passive"))
      (node (ref "D22") (pin "2") (pinfunction "A_2") (pintype "passive"))
      (node (ref "R12") (pin "2") (pinfunction "2_2") (pintype "passive"))
      (node (ref "R24") (pin "2") (pinfunction "2_2") (pintype "passive"))
    )
    (net (code "17") (name "GND_INA") (class "Default")
      (node (ref "C30") (pin "1") (pinfunction "1_1") (pintype "passive"))
      (node (ref "U8") (pin "2") (pinfunction "V-_2") (pintype "power_in"))
    )
    (net (code "18") (name "HV1") (class "Default")
      (node (ref "D21") (pin "2") (pinfunction "A_2") (pintype "passive"))
      (node (ref "F1") (pin "1") (pinfunction "1_1") (pintype "passive"))
      (node (ref "R22") (pin "2") (pinfunction "2_2") (pintype "passive"))
      (node (ref "UR1") (pin "3") (pinfunction "+_3") (pintype "passive"))
    )
    (net (code "19") (name "LED_PWM1") (class "Default")
      (node (ref "U1") (pin "2") (pinfunction "IN_2") (pintype "passive"))
    )
    (net (code "20") (name "LED_PWM2") (class "Default")
      (node (ref "U2") (pin "2") (pinfunction "IN_2") (pintype "passive"))
    )
    (net (code "21") (name "LED_PWM3") (class "Default")
      (node (ref "U3") (pin "2") (pinfunction "IN_2") (pintype "passive"))
    )
    (net (code "22") (name "LED_PWM4") (class "Default")
      (node (ref "U4") (pin "2") (pinfunction "IN_2") (pintype "passive"))
    )
    (net (code "23") (name "LED_PWM5") (class "Default")
      (node (ref "U7") (pin "2") (pinfunction "PWM_1_2") (pintype "passive"))
    )
    (net (code "24") (name "MCU_VCC") (class "Default")
      (node (ref "C13") (pin "2") (pinfunction "2_2") (pintype "passive"))
      (node (ref "C14") (pin "2") (pinfunction "2_2") (pintype "passive"))
      (node (ref "U6") (pin "2") (pinfunction "VOUT_2") (pintype "passive"))
      (node (ref "U6") (pin "4") (pinfunction "VOUT_4") (pintype "passive"))
    )
    (net (code "25") (name "Net-(C11-Pad1)") (class "Default")
      (node (ref "C11") (pin "1") (pinfunction "1_1") (pintype "passive"))
      (node (ref "CON2") (pin "2") (pinfunction "2_2") (pintype "passive"))
      (node (ref "RV1") (pin "2") (pinfunction "2_2") (pintype "passive"))
      (node (ref "UR1") (pin "2") (pinfunction "2_2") (pintype "passive"))
    )
    (net (code "26") (name "Net-(C11-Pad2)") (class "Default")
      (node (ref "C11") (pin "2") (pinfunction "2_2") (pintype "passive"))
      (node (ref "F2") (pin "1") (pinfunction "1_1") (pintype "passive"))
      (node (ref "RV1") (pin "1") (pinfunction "1_1") (pintype "passive"))
      (node (ref "UR1") (pin "1") (pinfunction "1_1") (pintype "passive"))
    )
    (net (code "27") (name "Net-(CON2-Pad1)") (class "Default")
      (node (ref "CON2") (pin "1") (pinfunction "1_1") (pintype "passive"))
      (node (ref "F2") (pin "2") (pinfunction "2_2") (pintype "passive"))
    )
    (net (code "28") (name "Net-(D1-K)") (class "Default")
      (node (ref "C4") (pin "2") (pinfunction "2_2") (pintype "passive"))
      (node (ref "C5") (pin "2") (pinfunction "2_2") (pintype "passive"))
      (node (ref "D1") (pin "1") (pinfunction "K_1") (pintype "passive"))
      (node (ref "U1") (pin "8") (pinfunction "VB_8") (pintype "passive"))
    )
    (net (code "29") (name "Net-(D2-A)") (class "Default")
      (node (ref "D2") (pin "2") (pinfunction "A_2") (pintype "passive"))
      (node (ref "D3") (pin "1") (pinfunction "K_1") (pintype "passive"))
      (node (ref "Q1") (pin "1") (pinfunction "G_1") (pintype "passive"))
      (node (ref "R1") (pin "1") (pinfunction "1_1") (pintype "passive"))
      (node (ref "R2") (pin "1") (pinfunction "1_1") (pintype "passive"))
    )
    (net (code "30") (name "Net-(D2-K)") (class "Default")
      (node (ref "D2") (pin "1") (pinfunction "K_1") (pintype "passive"))
      (node (ref "R2") (pin "2") (pinfunction "2_2") (pintype "passive"))
      (node (ref "U1") (pin "7") (pinfunction "HO_7") (pintype "passive"))
    )
    (net (code "31") (name "Net-(D4-K)") (class "Default")
      (node (ref "C18") (pin "2") (pinfunction "2_2") (pintype "passive"))
      (node (ref "C19") (pin "2") (pinfunction "2_2") (pintype "passive"))
      (node (ref "D4") (pin "1") (pinfunction "K_1") (pintype "passive"))
      (node (ref "U2") (pin "8") (pinfunction "VB_8") (pintype "passive"))
    )
    (net (code "32") (name "Net-(D5-A)") (class "Default")
      (node (ref "D5") (pin "2") (pinfunction "A_2") (pintype "passive"))
      (node (ref "D6") (pin "1") (pinfunction "K_1") (pintype "passive"))
      (node (ref "Q2") (pin "1") (pinfunction "G_1") (pintype "passive"))
      (node (ref "R3") (pin "1") (pinfunction "1_1") (pintype "passive"))
      (node (ref "R4") (pin "1") (pinfunction "1_1") (pintype "passive"))
    )
    (net (code "33") (name "Net-(D5-K)") (class "Default")
      (node (ref "D5") (pin "1") (pinfunction "K_1") (pintype "passive"))
      (node (ref "R4") (pin "2") (pinfunction "2_2") (pintype "passive"))
      (node (ref "U2") (pin "7") (pinfunction "HO_7") (pintype "passive"))
    )
    (net (code "34") (name "Net-(D7-K)") (class "Default")
      (node (ref "C22") (pin "2") (pinfunction "2_2") (pintype "passive"))
      (node (ref "C23") (pin "2") (pinfunction "2_2") (pintype "passive"))
      (node (ref "D7") (pin "1") (pinfunction "K_1") (pintype "passive"))
      (node (ref "U3") (pin "8") (pinfunction "VB_8") (pintype "passive"))
    )
    (net (code "35") (name "Net-(D8-A)") (class "Default")
      (node (ref "D8") (pin "2") (pinfunction "A_2") (pintype "passive"))
      (node (ref "D9") (pin "1") (pinfunction "K_1") (pintype "passive"))
      (node (ref "Q3") (pin "1") (pinfunction "G_1") (pintype "passive"))
      (node (ref "R5") (pin "1") (pinfunction "1_1") (pintype "passive"))
      (node (ref "R6") (pin "1") (pinfunction "1_1") (pintype "passive"))
    )
    (net (code "36") (name "Net-(D8-K)") (class "Default")
      (node (ref "D8") (pin "1") (pinfunction "K_1") (pintype "passive"))
      (node (ref "R6") (pin "2") (pinfunction "2_2") (pintype "passive"))
      (node (ref "U3") (pin "7") (pinfunction "HO_7") (pintype "passive"))
    )
    (net (code "37") (name "Net-(D10-K)") (class "Default")
      (node (ref "C26") (pin "2") (pinfunction "2_2") (pintype "passive"))
      (node (ref "C27") (pin "2") (pinfunction "2_2") (pintype "passive"))
      (node (ref "D10") (pin "1") (pinfunction "K_1") (pintype "passive"))
      (node (ref "U4") (pin "8") (pinfunction "VB_8") (pintype "passive"))
    )
    (net (code "38") (name "Net-(D11-A)") (class "Default")
      (node (ref "D11") (pin "2") (pinfunction "A_2") (pintype "passive"))
      (node (ref "D12") (pin "1") (pinfunction "K_1") (pintype "passive"))
      (node (ref "Q4") (pin "1") (pinfunction "G_1") (pintype "passive"))
      (node (ref "R7") (pin "1") (pinfunction "1_1") (pintype "passive"))
      (node (ref "R8") (pin "1") (pinfunction "1_1") (pintype "passive"))
    )
    (net (code "39") (name "Net-(D11-K)") (class "Default")
      (node (ref "D11") (pin "1") (pinfunction "K_1") (pintype "passive"))
      (node (ref "R8") (pin "2") (pinfunction "2_2") (pintype "passive"))
      (node (ref "U4") (pin "7") (pinfunction "HO_7") (pintype "passive"))
    )
    (net (code "40") (name "Net-(D13-A)") (class "Default")
      (node (ref "D13") (pin "2") (pinfunction "A_2") (pintype "passive"))
      (node (ref "D14") (pin "1") (pinfunction "K_1") (pintype "passive"))
      (node (ref "Q5") (pin "1") (pinfunction "G_1") (pintype "passive"))
      (node (ref "R10") (pin "1") (pinfunction "1_1") (pintype "passive"))
      (node (ref "R9") (pin "1") (pinfunction "1_1") (pintype "passive"))
    )
    (net (code "41") (name "Net-(D13-K)") (class "Default")
      (node (ref "D13") (pin "1") (pinfunction "K_1") (pintype "passive"))
      (node (ref "R10") (pin "2") (pinfunction "2_2") (pintype "passive"))
      (node (ref "U7") (pin "7") (pinfunction "OUT_1_7") (pintype "passive"))
    )
    (net (code "42") (name "Net-(D17-A)") (class "Default")
      (node (ref "D17") (pin "2") (pinfunction "A_2") (pintype "passive"))
      (node (ref "F1") (pin "2") (pinfunction "2_2") (pintype "passive"))
    )
    (net (code "43") (name "Net-(D18-K)") (class "Default")
      (node (ref "C6") (pin "1") (pinfunction "1_1") (pintype "passive"))
      (node (ref "D18") (pin "1") (pinfunction "K_1") (pintype "passive"))
      (node (ref "R17") (pin "2") (pinfunction "2_2") (pintype "passive"))
    )
    (net (code "44") (name "Net-(R22-Pad1)") (class "Default")
      (node (ref "R22") (pin "1") (pinfunction "1_1") (pintype "passive"))
      (node (ref "R23") (pin "1") (pinfunction "1_1") (pintype "passive"))
    )
    (net (code "45") (name "Net-(R23-Pad2)") (class "Default")
      (node (ref "R23") (pin "2") (pinfunction "2_2") (pintype "passive"))
      (node (ref "R25") (pin "2") (pinfunction "2_2") (pintype "passive"))
    )
    (net (code "46") (name "unconnected-(U1-NC-Pad3)") (class "Default")
      (node (ref "U1") (pin "3") (pinfunction "NC_3") (pintype "passive+no_connect"))
    )
    (net (code "47") (name "unconnected-(U1-NC-Pad5)") (class "Default")
      (node (ref "U1") (pin "5") (pinfunction "NC_5") (pintype "passive+no_connect"))
    )
    (net (code "48") (name "unconnected-(U2-NC-Pad3)") (class "Default")
      (node (ref "U2") (pin "3") (pinfunction "NC_3") (pintype "passive+no_connect"))
    )
    (net (code "49") (name "unconnected-(U2-NC-Pad5)") (class "Default")
      (node (ref "U2") (pin "5") (pinfunction "NC_5") (pintype "passive+no_connect"))
    )
    (net (code "50") (name "unconnected-(U2-VS-Pad6)") (class "Default")
      (node (ref "U2") (pin "6") (pinfunction "VS_6") (pintype "passive"))
    )
    (net (code "51") (name "unconnected-(U3-NC-Pad3)") (class "Default")
      (node (ref "U3") (pin "3") (pinfunction "NC_3") (pintype "passive+no_connect"))
    )
    (net (code "52") (name "unconnected-(U3-NC-Pad5)") (class "Default")
      (node (ref "U3") (pin "5") (pinfunction "NC_5") (pintype "passive+no_connect"))
    )
    (net (code "53") (name "unconnected-(U3-VS-Pad6)") (class "Default")
      (node (ref "U3") (pin "6") (pinfunction "VS_6") (pintype "passive"))
    )
    (net (code "54") (name "unconnected-(U4-NC-Pad3)") (class "Default")
      (node (ref "U4") (pin "3") (pinfunction "NC_3") (pintype "passive+no_connect"))
    )
    (net (code "55") (name "unconnected-(U4-NC-Pad5)") (class "Default")
      (node (ref "U4") (pin "5") (pinfunction "NC_5") (pintype "passive+no_connect"))
    )
    (net (code "56") (name "unconnected-(U4-VS-Pad6)") (class "Default")
      (node (ref "U4") (pin "6") (pinfunction "VS_6") (pintype "passive"))
    )
    (net (code "57") (name "unconnected-(U7-OUT_2-Pad5)") (class "Default")
      (node (ref "U7") (pin "5") (pinfunction "OUT_2_5") (pintype "passive"))
    )
    (net (code "58") (name "unconnected-(U7-PWM_2-Pad4)") (class "Default")
      (node (ref "U7") (pin "4") (pinfunction "PWM_2_4") (pintype "passive"))
    )
  )
)
